# MRCS-Dual-3-Position-Semaphore-Controlle.net
KiCad netlist of a schematic drawn in EAGLE
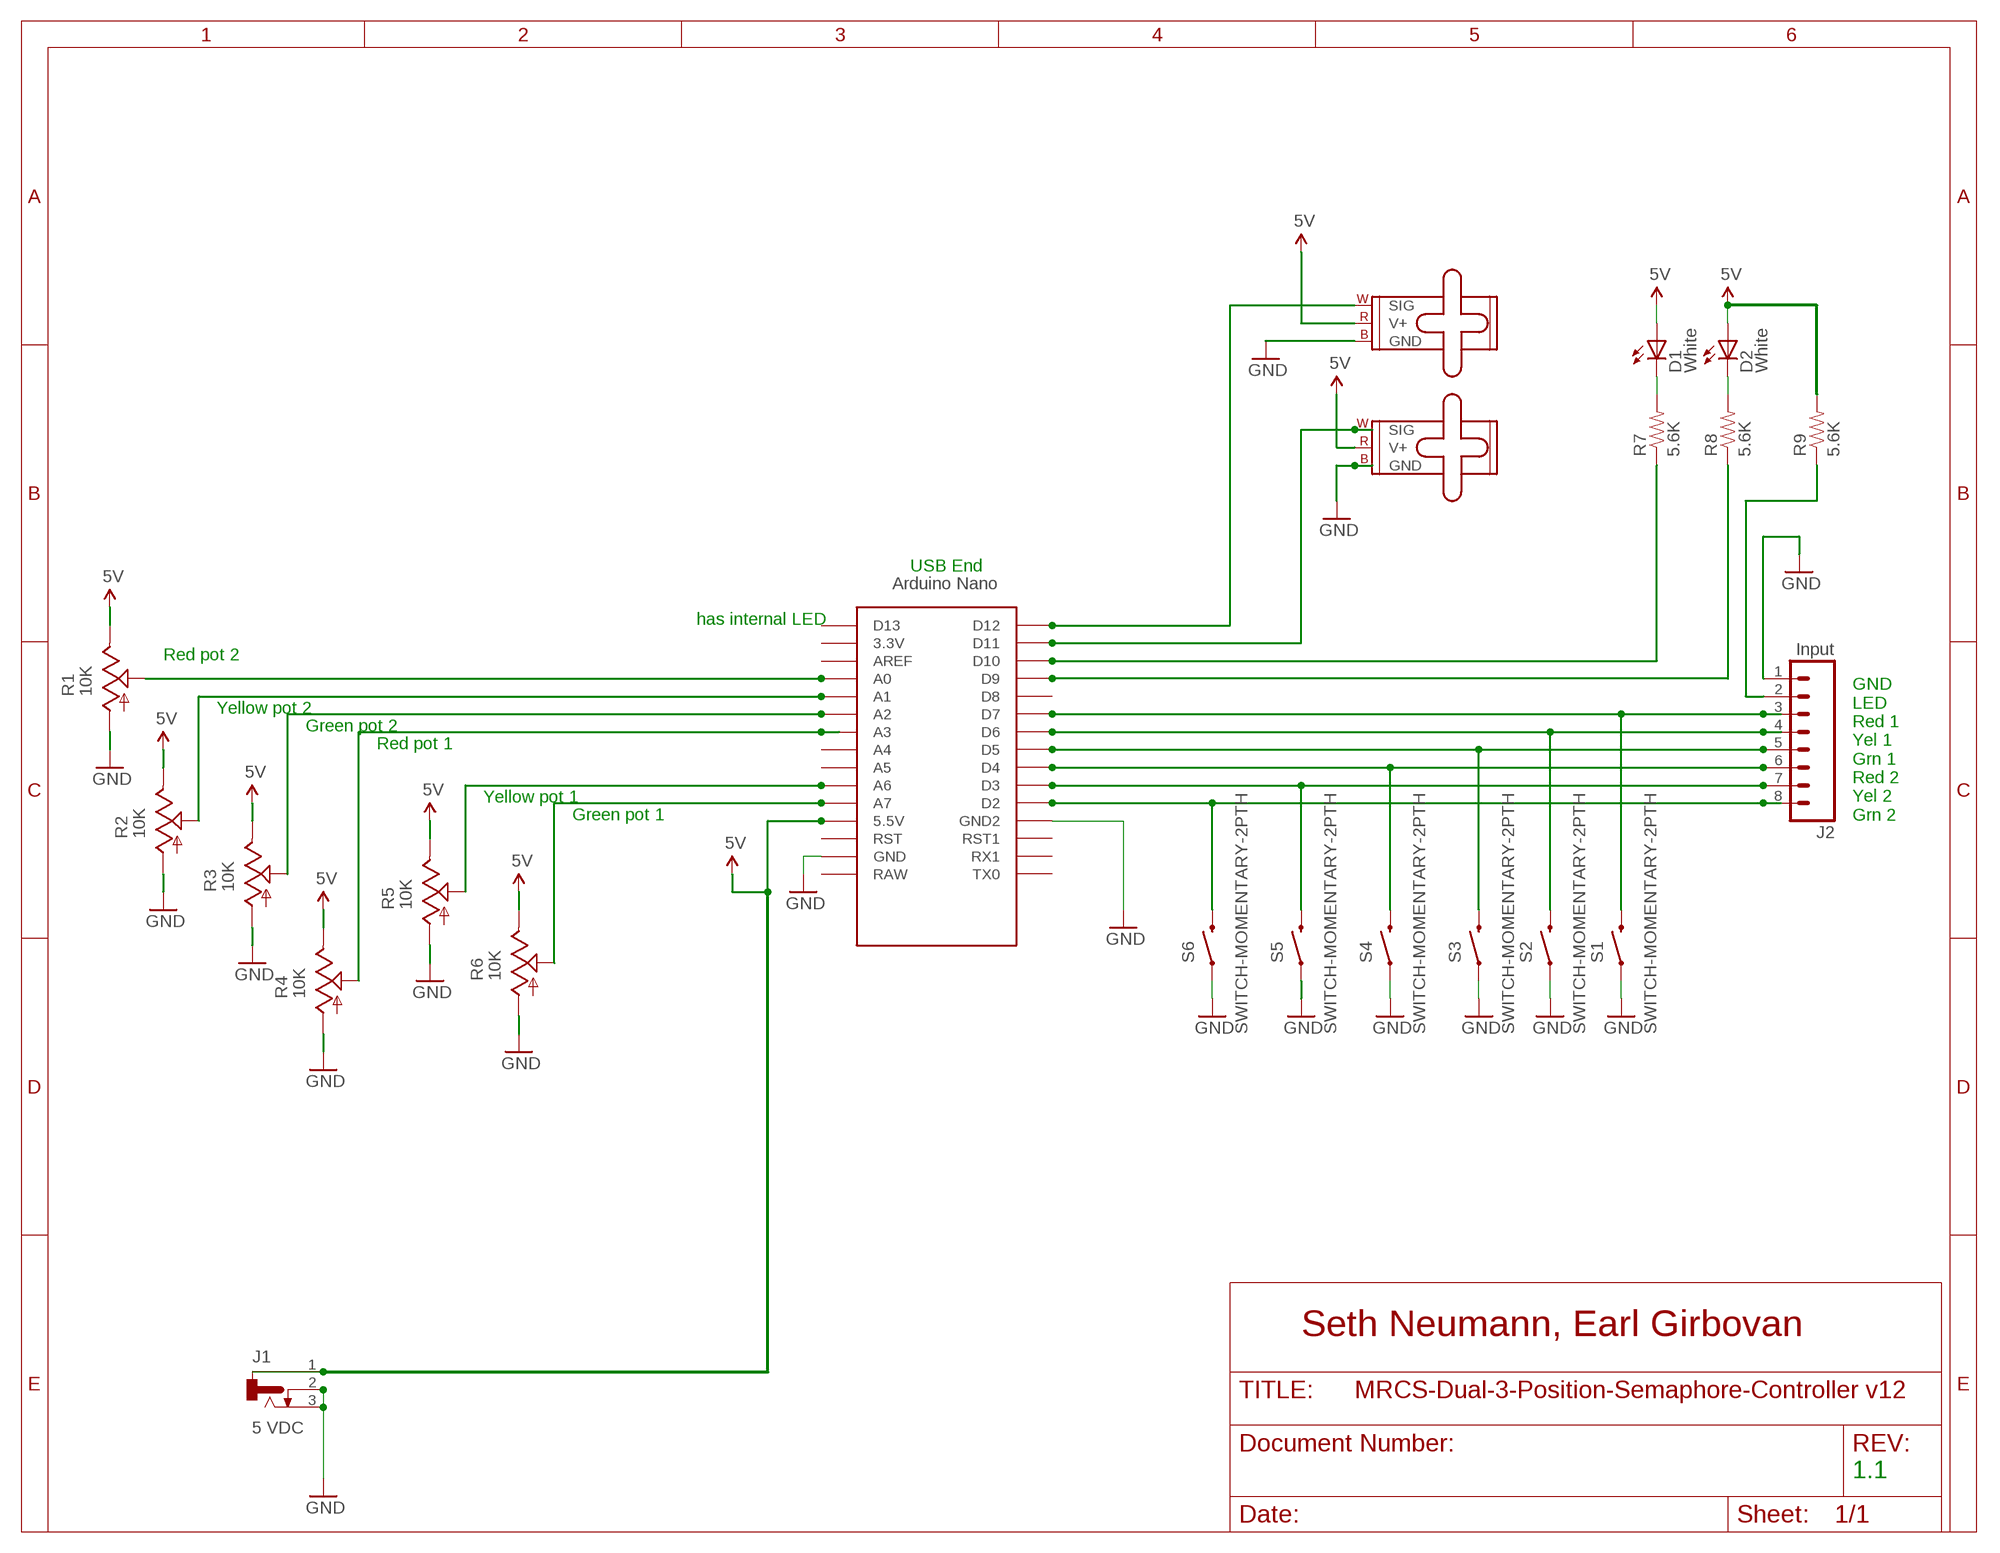
[diagram p0: schematic, sheet 1]

(export (version "E")
  (design (tool "Eeschema 10.0.6"))
  (components
    (comp (ref "D1")
      (value "White")
      (footprint "eagle-import:LED3MM")
      (libsource (lib "eagle-import") (part "LEDLED3MM"))
    )
    (comp (ref "D2")
      (value "White")
      (footprint "eagle-import:LED3MM")
      (libsource (lib "eagle-import") (part "LEDLED3MM"))
    )
    (comp (ref "J1")
      (value "5 VDC")
      (footprint "eagle-import:DCJ0202")
      (libsource (lib "eagle-import") (part "CONNECTOR-DC-POWER-RA"))
    )
    (comp (ref "J2")
      (value "Input")
      (footprint "eagle-import:1X08_LOCK")
      (libsource (lib "eagle-import") (part "CONNECTOR-M08LOCK"))
    )
    (comp (ref "M1")
      (value "SMALL_SERVO")
      (footprint "eagle-import:1X03")
      (libsource (lib "eagle-import") (part "SMALL_SERVO"))
    )
    (comp (ref "M2")
      (value "SMALL_SERVO")
      (footprint "eagle-import:1X03")
      (libsource (lib "eagle-import") (part "SMALL_SERVO"))
    )
    (comp (ref "NANO")
      (value "NANO")
      (footprint "eagle-import:NANO")
      (libsource (lib "eagle-import") (part "NANO"))
    )
    (comp (ref "R1")
      (value "10K")
      (footprint "eagle-import:RS3")
      (libsource (lib "eagle-import") (part "TRIM_US-RS3"))
    )
    (comp (ref "R2")
      (value "10K")
      (footprint "eagle-import:RS3")
      (libsource (lib "eagle-import") (part "TRIM_US-RS3"))
    )
    (comp (ref "R3")
      (value "10K")
      (footprint "eagle-import:RS3")
      (libsource (lib "eagle-import") (part "TRIM_US-RS3"))
    )
    (comp (ref "R4")
      (value "10K")
      (footprint "eagle-import:RS3")
      (libsource (lib "eagle-import") (part "TRIM_US-RS3"))
    )
    (comp (ref "R5")
      (value "10K")
      (footprint "eagle-import:RS3")
      (libsource (lib "eagle-import") (part "TRIM_US-RS3"))
    )
    (comp (ref "R6")
      (value "10K")
      (footprint "eagle-import:RS3")
      (libsource (lib "eagle-import") (part "TRIM_US-RS3"))
    )
    (comp (ref "R7")
      (value "5.6K")
      (footprint "eagle-import:AXIAL-0.4")
      (libsource (lib "eagle-import") (part "RESISTORPTH-1/4W"))
    )
    (comp (ref "R8")
      (value "5.6K")
      (footprint "eagle-import:AXIAL-0.4")
      (libsource (lib "eagle-import") (part "RESISTORPTH-1/4W"))
    )
    (comp (ref "R9")
      (value "5.6K")
      (footprint "eagle-import:AXIAL-0.4")
      (libsource (lib "eagle-import") (part "RESISTORPTH-1/4W"))
    )
    (comp (ref "S1")
      (value "SWITCH-MOMENTARY-2PTH")
      (footprint "eagle-import:TACTILE-PTH")
      (libsource (lib "eagle-import") (part "SWITCH-MOMENTARY-2PTH"))
    )
    (comp (ref "S2")
      (value "SWITCH-MOMENTARY-2PTH")
      (footprint "eagle-import:TACTILE-PTH")
      (libsource (lib "eagle-import") (part "SWITCH-MOMENTARY-2PTH"))
    )
    (comp (ref "S3")
      (value "SWITCH-MOMENTARY-2PTH")
      (footprint "eagle-import:TACTILE-PTH")
      (libsource (lib "eagle-import") (part "SWITCH-MOMENTARY-2PTH"))
    )
    (comp (ref "S4")
      (value "SWITCH-MOMENTARY-2PTH")
      (footprint "eagle-import:TACTILE-PTH")
      (libsource (lib "eagle-import") (part "SWITCH-MOMENTARY-2PTH"))
    )
    (comp (ref "S5")
      (value "SWITCH-MOMENTARY-2PTH")
      (footprint "eagle-import:TACTILE-PTH")
      (libsource (lib "eagle-import") (part "SWITCH-MOMENTARY-2PTH"))
    )
    (comp (ref "S6")
      (value "SWITCH-MOMENTARY-2PTH")
      (footprint "eagle-import:TACTILE-PTH")
      (libsource (lib "eagle-import") (part "SWITCH-MOMENTARY-2PTH"))
    )
  )
  (nets
    (net (code "1") (name "5V") (class "Default")
      (node (ref "D1") (pin "A") (pinfunction "A_A") (pintype "passive"))
      (node (ref "D2") (pin "A") (pinfunction "A_A") (pintype "passive"))
      (node (ref "J1") (pin "1") (pinfunction "1_1") (pintype "passive"))
      (node (ref "M1") (pin "2") (pinfunction "V+_2") (pintype "bidirectional"))
      (node (ref "M2") (pin "2") (pinfunction "V+_2") (pintype "bidirectional"))
      (node (ref "NANO") (pin "5V") (pinfunction "5.5V_5V") (pintype "bidirectional"))
      (node (ref "R1") (pin "E") (pinfunction "E_E") (pintype "passive"))
      (node (ref "R2") (pin "E") (pinfunction "E_E") (pintype "passive"))
      (node (ref "R3") (pin "E") (pinfunction "E_E") (pintype "passive"))
      (node (ref "R4") (pin "E") (pinfunction "E_E") (pintype "passive"))
      (node (ref "R5") (pin "E") (pinfunction "E_E") (pintype "passive"))
      (node (ref "R6") (pin "E") (pinfunction "E_E") (pintype "passive"))
      (node (ref "R9") (pin "P$2") (pinfunction "2_P$2") (pintype "passive"))
    )
    (net (code "2") (name "GND") (class "Default")
      (node (ref "J1") (pin "2") (pinfunction "2_2") (pintype "passive"))
      (node (ref "J1") (pin "3") (pinfunction "3_3") (pintype "passive"))
      (node (ref "J2") (pin "1") (pinfunction "1_1") (pintype "passive"))
      (node (ref "M1") (pin "3") (pinfunction "GND_3") (pintype "bidirectional"))
      (node (ref "M2") (pin "3") (pinfunction "GND_3") (pintype "bidirectional"))
      (node (ref "NANO") (pin "GND") (pinfunction "GND_GND") (pintype "bidirectional"))
      (node (ref "NANO") (pin "GND1") (pinfunction "GND2_GND1") (pintype "bidirectional"))
      (node (ref "R1") (pin "A") (pinfunction "A_A") (pintype "passive"))
      (node (ref "R2") (pin "A") (pinfunction "A_A") (pintype "passive"))
      (node (ref "R3") (pin "A") (pinfunction "A_A") (pintype "passive"))
      (node (ref "R4") (pin "A") (pinfunction "A_A") (pintype "passive"))
      (node (ref "R5") (pin "A") (pinfunction "A_A") (pintype "passive"))
      (node (ref "R6") (pin "A") (pinfunction "A_A") (pintype "passive"))
      (node (ref "S1") (pin "1") (pinfunction "1_1") (pintype "passive"))
      (node (ref "S2") (pin "1") (pinfunction "1_1") (pintype "passive"))
      (node (ref "S3") (pin "1") (pinfunction "1_1") (pintype "passive"))
      (node (ref "S4") (pin "1") (pinfunction "1_1") (pintype "passive"))
      (node (ref "S5") (pin "1") (pinfunction "1_1") (pintype "passive"))
      (node (ref "S6") (pin "1") (pinfunction "1_1") (pintype "passive"))
    )
    (net (code "3") (name "Net-(D1-C)") (class "Default")
      (node (ref "D1") (pin "K") (pinfunction "C_K") (pintype "passive"))
      (node (ref "R7") (pin "P$2") (pinfunction "2_P$2") (pintype "passive"))
    )
    (net (code "4") (name "Net-(D2-C)") (class "Default")
      (node (ref "D2") (pin "K") (pinfunction "C_K") (pintype "passive"))
      (node (ref "R8") (pin "P$2") (pinfunction "2_P$2") (pintype "passive"))
    )
    (net (code "5") (name "Net-(M1-SIG)") (class "Default")
      (node (ref "M1") (pin "1") (pinfunction "SIG_1") (pintype "bidirectional"))
      (node (ref "NANO") (pin "D12") (pinfunction "D12_D12") (pintype "bidirectional"))
    )
    (net (code "6") (name "Net-(M2-SIG)") (class "Default")
      (node (ref "M2") (pin "1") (pinfunction "SIG_1") (pintype "bidirectional"))
      (node (ref "NANO") (pin "D11") (pinfunction "D11_D11") (pintype "bidirectional"))
    )
    (net (code "7") (name "Net-(NANO-PadA0)") (class "Default")
      (node (ref "NANO") (pin "A0") (pinfunction "A0_A0") (pintype "bidirectional"))
      (node (ref "R1") (pin "S") (pinfunction "S_S") (pintype "passive"))
    )
    (net (code "8") (name "Net-(NANO-PadA1)") (class "Default")
      (node (ref "NANO") (pin "A1") (pinfunction "A1_A1") (pintype "bidirectional"))
      (node (ref "R2") (pin "S") (pinfunction "S_S") (pintype "passive"))
    )
    (net (code "9") (name "Net-(NANO-PadA2)") (class "Default")
      (node (ref "NANO") (pin "A2") (pinfunction "A2_A2") (pintype "bidirectional"))
      (node (ref "R3") (pin "S") (pinfunction "S_S") (pintype "passive"))
    )
    (net (code "10") (name "Net-(NANO-PadA3)") (class "Default")
      (node (ref "NANO") (pin "A3") (pinfunction "A3_A3") (pintype "bidirectional"))
      (node (ref "R4") (pin "S") (pinfunction "S_S") (pintype "passive"))
    )
    (net (code "11") (name "Net-(NANO-PadA6)") (class "Default")
      (node (ref "NANO") (pin "A6") (pinfunction "A6_A6") (pintype "bidirectional"))
      (node (ref "R5") (pin "S") (pinfunction "S_S") (pintype "passive"))
    )
    (net (code "12") (name "Net-(NANO-PadA7)") (class "Default")
      (node (ref "NANO") (pin "A7") (pinfunction "A7_A7") (pintype "bidirectional"))
      (node (ref "R6") (pin "S") (pinfunction "S_S") (pintype "passive"))
    )
    (net (code "13") (name "Net-(R7-1)") (class "Default")
      (node (ref "NANO") (pin "D10") (pinfunction "D10_D10") (pintype "bidirectional"))
      (node (ref "R7") (pin "P$1") (pinfunction "1_P$1") (pintype "passive"))
    )
    (net (code "14") (name "Net-(R8-1)") (class "Default")
      (node (ref "NANO") (pin "D9") (pinfunction "D9_D9") (pintype "bidirectional"))
      (node (ref "R8") (pin "P$1") (pinfunction "1_P$1") (pintype "passive"))
    )
    (net (code "15") (name "Net-(R9-1)") (class "Default")
      (node (ref "J2") (pin "2") (pinfunction "2_2") (pintype "passive"))
      (node (ref "R9") (pin "P$1") (pinfunction "1_P$1") (pintype "passive"))
    )
    (net (code "16") (name "Net-(S1-2)") (class "Default")
      (node (ref "J2") (pin "3") (pinfunction "3_3") (pintype "passive"))
      (node (ref "NANO") (pin "D7") (pinfunction "D7_D7") (pintype "bidirectional"))
      (node (ref "S1") (pin "3") (pinfunction "2_3") (pintype "passive"))
    )
    (net (code "17") (name "Net-(S2-2)") (class "Default")
      (node (ref "J2") (pin "4") (pinfunction "4_4") (pintype "passive"))
      (node (ref "NANO") (pin "D6") (pinfunction "D6_D6") (pintype "bidirectional"))
      (node (ref "S2") (pin "3") (pinfunction "2_3") (pintype "passive"))
    )
    (net (code "18") (name "Net-(S3-2)") (class "Default")
      (node (ref "J2") (pin "5") (pinfunction "5_5") (pintype "passive"))
      (node (ref "NANO") (pin "D5") (pinfunction "D5_D5") (pintype "bidirectional"))
      (node (ref "S3") (pin "3") (pinfunction "2_3") (pintype "passive"))
    )
    (net (code "19") (name "Net-(S4-2)") (class "Default")
      (node (ref "J2") (pin "6") (pinfunction "6_6") (pintype "passive"))
      (node (ref "NANO") (pin "D4") (pinfunction "D4_D4") (pintype "bidirectional"))
      (node (ref "S4") (pin "3") (pinfunction "2_3") (pintype "passive"))
    )
    (net (code "20") (name "Net-(S5-2)") (class "Default")
      (node (ref "J2") (pin "7") (pinfunction "7_7") (pintype "passive"))
      (node (ref "NANO") (pin "D3") (pinfunction "D3_D3") (pintype "bidirectional"))
      (node (ref "S5") (pin "3") (pinfunction "2_3") (pintype "passive"))
    )
    (net (code "21") (name "Net-(S6-2)") (class "Default")
      (node (ref "J2") (pin "8") (pinfunction "8_8") (pintype "passive"))
      (node (ref "NANO") (pin "D2") (pinfunction "D2_D2") (pintype "bidirectional"))
      (node (ref "S6") (pin "3") (pinfunction "2_3") (pintype "passive"))
    )
    (net (code "22") (name "unconnected-(NANO-Pad3.3V)") (class "Default")
      (node (ref "NANO") (pin "3.3V") (pinfunction "3.3V_3.3V") (pintype "bidirectional"))
    )
    (net (code "23") (name "unconnected-(NANO-PadA4)") (class "Default")
      (node (ref "NANO") (pin "A4") (pinfunction "A4_A4") (pintype "bidirectional"))
    )
    (net (code "24") (name "unconnected-(NANO-PadA5)") (class "Default")
      (node (ref "NANO") (pin "A5") (pinfunction "A5_A5") (pintype "bidirectional"))
    )
    (net (code "25") (name "unconnected-(NANO-PadAREF)") (class "Default")
      (node (ref "NANO") (pin "AREF") (pinfunction "AREF_AREF") (pintype "bidirectional"))
    )
    (net (code "26") (name "unconnected-(NANO-PadD8)") (class "Default")
      (node (ref "NANO") (pin "D8") (pinfunction "D8_D8") (pintype "bidirectional"))
    )
    (net (code "27") (name "unconnected-(NANO-PadD13)") (class "Default")
      (node (ref "NANO") (pin "D13") (pinfunction "D13_D13") (pintype "bidirectional"))
    )
    (net (code "28") (name "unconnected-(NANO-PadRAW)") (class "Default")
      (node (ref "NANO") (pin "RAW") (pinfunction "RAW_RAW") (pintype "bidirectional"))
    )
    (net (code "29") (name "unconnected-(NANO-PadRST)") (class "Default")
      (node (ref "NANO") (pin "RST") (pinfunction "RST_RST") (pintype "bidirectional"))
    )
    (net (code "30") (name "unconnected-(NANO-PadRST1)") (class "Default")
      (node (ref "NANO") (pin "RST1") (pinfunction "RST1_RST1") (pintype "bidirectional"))
    )
    (net (code "31") (name "unconnected-(NANO-PadRX1)") (class "Default")
      (node (ref "NANO") (pin "RX1") (pinfunction "RX1_RX1") (pintype "bidirectional"))
    )
    (net (code "32") (name "unconnected-(NANO-PadTX0)") (class "Default")
      (node (ref "NANO") (pin "TX0") (pinfunction "TX0_TX0") (pintype "bidirectional"))
    )
  )
)
